# PwrSel.net
KiCad netlist of a schematic drawn in Altium Designer
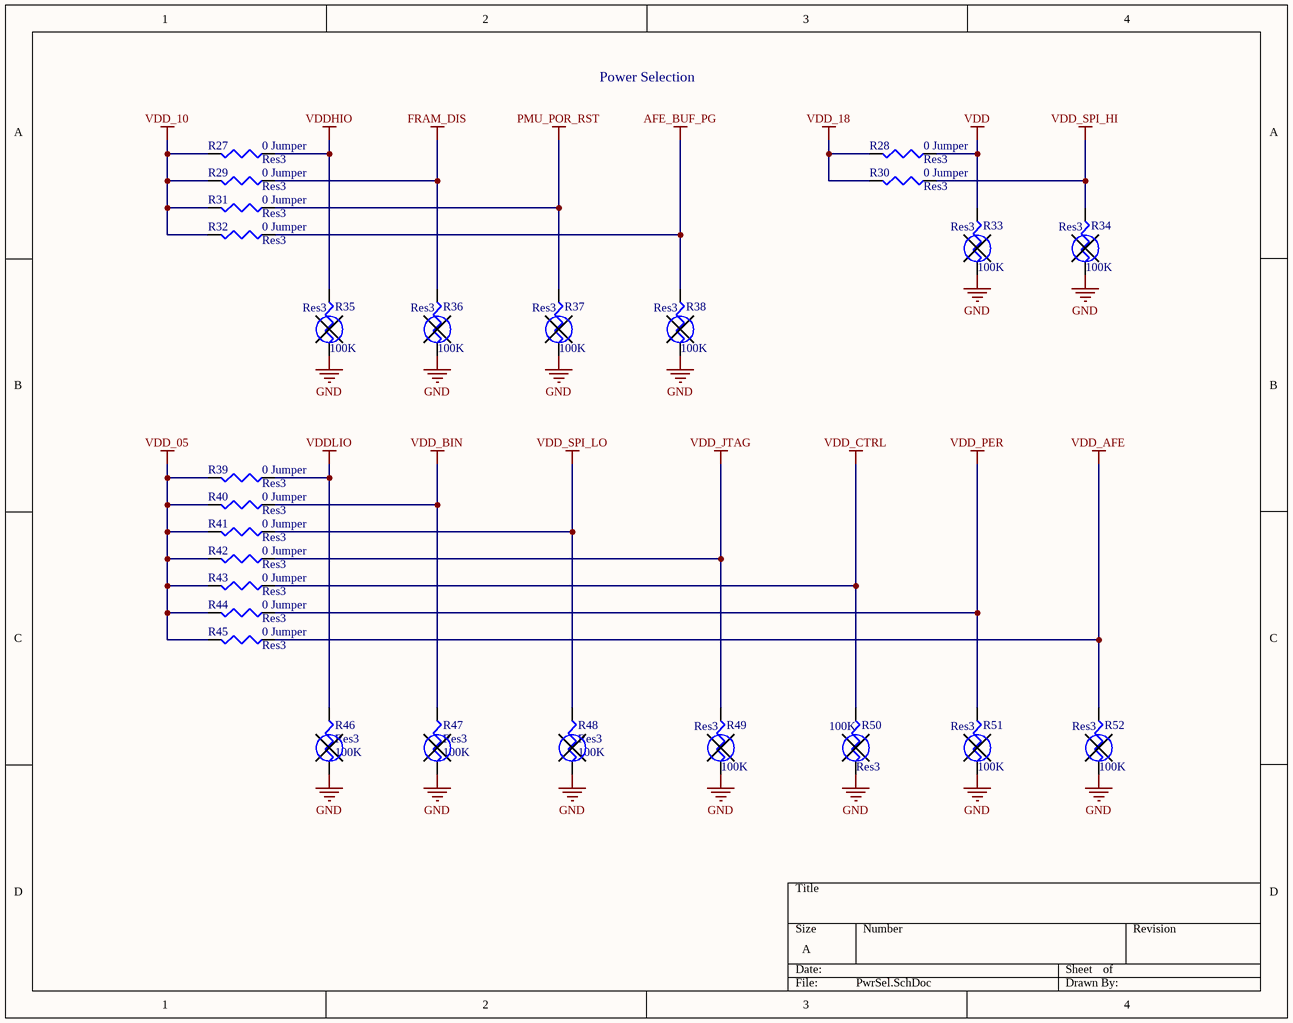
[diagram p0: PwrSel.SchDoc]

(export (version "E")
  (design (tool "Eeschema 10.0.6"))
  (components
    (comp (ref "R27")
      (value "Res3")
      (footprint "0402")
      (description "Resistor")
      (fields (field (name "ALTIUM_VALUE") "0 Jumper") (field (name "PUBLISHER") "Altium Limited"))
      (libsource (lib "Miscellaneous Devices") (part "Res3"))
    )
    (comp (ref "R28")
      (value "Res3")
      (footprint "0402")
      (description "Resistor")
      (fields (field (name "ALTIUM_VALUE") "0 Jumper") (field (name "PUBLISHER") "Altium Limited"))
      (libsource (lib "Miscellaneous Devices") (part "Res3"))
    )
    (comp (ref "R29")
      (value "Res3")
      (footprint "0402")
      (description "Resistor")
      (fields (field (name "ALTIUM_VALUE") "0 Jumper") (field (name "PUBLISHER") "Altium Limited"))
      (libsource (lib "Miscellaneous Devices") (part "Res3"))
    )
    (comp (ref "R30")
      (value "Res3")
      (footprint "0402")
      (description "Resistor")
      (fields (field (name "ALTIUM_VALUE") "0 Jumper") (field (name "PUBLISHER") "Altium Limited"))
      (libsource (lib "Miscellaneous Devices") (part "Res3"))
    )
    (comp (ref "R31")
      (value "Res3")
      (footprint "0402")
      (description "Resistor")
      (fields (field (name "ALTIUM_VALUE") "0 Jumper") (field (name "PUBLISHER") "Altium Limited"))
      (libsource (lib "Miscellaneous Devices") (part "Res3"))
    )
    (comp (ref "R32")
      (value "Res3")
      (footprint "0402")
      (description "Resistor")
      (fields (field (name "ALTIUM_VALUE") "0 Jumper") (field (name "PUBLISHER") "Altium Limited"))
      (libsource (lib "Miscellaneous Devices") (part "Res3"))
    )
    (comp (ref "R33")
      (value "Res3")
      (footprint "0402")
      (description "Resistor")
      (fields (field (name "ALTIUM_VALUE") "100K") (field (name "PUBLISHER") "Altium Limited"))
      (libsource (lib "Miscellaneous Devices") (part "Res3"))
    )
    (comp (ref "R34")
      (value "Res3")
      (footprint "0402")
      (description "Resistor")
      (fields (field (name "ALTIUM_VALUE") "100K") (field (name "PUBLISHER") "Altium Limited"))
      (libsource (lib "Miscellaneous Devices") (part "Res3"))
    )
    (comp (ref "R35")
      (value "Res3")
      (footprint "0402")
      (description "Resistor")
      (fields (field (name "ALTIUM_VALUE") "100K") (field (name "PUBLISHER") "Altium Limited"))
      (libsource (lib "Miscellaneous Devices") (part "Res3"))
    )
    (comp (ref "R36")
      (value "Res3")
      (footprint "0402")
      (description "Resistor")
      (fields (field (name "ALTIUM_VALUE") "100K") (field (name "PUBLISHER") "Altium Limited"))
      (libsource (lib "Miscellaneous Devices") (part "Res3"))
    )
    (comp (ref "R37")
      (value "Res3")
      (footprint "0402")
      (description "Resistor")
      (fields (field (name "ALTIUM_VALUE") "100K") (field (name "PUBLISHER") "Altium Limited"))
      (libsource (lib "Miscellaneous Devices") (part "Res3"))
    )
    (comp (ref "R38")
      (value "Res3")
      (footprint "0402")
      (description "Resistor")
      (fields (field (name "ALTIUM_VALUE") "100K") (field (name "PUBLISHER") "Altium Limited"))
      (libsource (lib "Miscellaneous Devices") (part "Res3"))
    )
    (comp (ref "R39")
      (value "Res3")
      (footprint "0402")
      (description "Resistor")
      (fields (field (name "ALTIUM_VALUE") "0 Jumper") (field (name "PUBLISHER") "Altium Limited"))
      (libsource (lib "Miscellaneous Devices") (part "Res3"))
    )
    (comp (ref "R40")
      (value "Res3")
      (footprint "0402")
      (description "Resistor")
      (fields (field (name "ALTIUM_VALUE") "0 Jumper") (field (name "PUBLISHER") "Altium Limited"))
      (libsource (lib "Miscellaneous Devices") (part "Res3"))
    )
    (comp (ref "R41")
      (value "Res3")
      (footprint "0402")
      (description "Resistor")
      (fields (field (name "ALTIUM_VALUE") "0 Jumper") (field (name "PUBLISHER") "Altium Limited"))
      (libsource (lib "Miscellaneous Devices") (part "Res3"))
    )
    (comp (ref "R42")
      (value "Res3")
      (footprint "0402")
      (description "Resistor")
      (fields (field (name "ALTIUM_VALUE") "0 Jumper") (field (name "PUBLISHER") "Altium Limited"))
      (libsource (lib "Miscellaneous Devices") (part "Res3"))
    )
    (comp (ref "R43")
      (value "Res3")
      (footprint "0402")
      (description "Resistor")
      (fields (field (name "ALTIUM_VALUE") "0 Jumper") (field (name "PUBLISHER") "Altium Limited"))
      (libsource (lib "Miscellaneous Devices") (part "Res3"))
    )
    (comp (ref "R44")
      (value "Res3")
      (footprint "0402")
      (description "Resistor")
      (fields (field (name "ALTIUM_VALUE") "0 Jumper") (field (name "PUBLISHER") "Altium Limited"))
      (libsource (lib "Miscellaneous Devices") (part "Res3"))
    )
    (comp (ref "R45")
      (value "Res3")
      (footprint "0402")
      (description "Resistor")
      (fields (field (name "ALTIUM_VALUE") "0 Jumper") (field (name "PUBLISHER") "Altium Limited"))
      (libsource (lib "Miscellaneous Devices") (part "Res3"))
    )
    (comp (ref "R46")
      (value "Res3")
      (footprint "0402")
      (description "Resistor")
      (fields (field (name "ALTIUM_VALUE") "100K") (field (name "PUBLISHER") "Altium Limited"))
      (libsource (lib "Miscellaneous Devices") (part "Res3"))
    )
    (comp (ref "R47")
      (value "Res3")
      (footprint "0402")
      (description "Resistor")
      (fields (field (name "ALTIUM_VALUE") "100K") (field (name "PUBLISHER") "Altium Limited"))
      (libsource (lib "Miscellaneous Devices") (part "Res3"))
    )
    (comp (ref "R48")
      (value "Res3")
      (footprint "0402")
      (description "Resistor")
      (fields (field (name "ALTIUM_VALUE") "100K") (field (name "PUBLISHER") "Altium Limited"))
      (libsource (lib "Miscellaneous Devices") (part "Res3"))
    )
    (comp (ref "R49")
      (value "Res3")
      (footprint "0402")
      (description "Resistor")
      (fields (field (name "ALTIUM_VALUE") "100K") (field (name "PUBLISHER") "Altium Limited"))
      (libsource (lib "Miscellaneous Devices") (part "Res3"))
    )
    (comp (ref "R50")
      (value "Res3")
      (footprint "0402")
      (description "Resistor")
      (fields (field (name "ALTIUM_VALUE") "100K") (field (name "PUBLISHER") "Altium Limited"))
      (libsource (lib "Miscellaneous Devices") (part "Res3"))
    )
    (comp (ref "R51")
      (value "Res3")
      (footprint "0402")
      (description "Resistor")
      (fields (field (name "ALTIUM_VALUE") "100K") (field (name "PUBLISHER") "Altium Limited"))
      (libsource (lib "Miscellaneous Devices") (part "Res3"))
    )
    (comp (ref "R52")
      (value "Res3")
      (footprint "0402")
      (description "Resistor")
      (fields (field (name "ALTIUM_VALUE") "100K") (field (name "PUBLISHER") "Altium Limited"))
      (libsource (lib "Miscellaneous Devices") (part "Res3"))
    )
  )
  (nets
    (net (code "1") (name "AFE_BUF_PG") (class "Default")
      (node (ref "R32") (pin "1") (pinfunction "1_1") (pintype "passive"))
      (node (ref "R38") (pin "1") (pinfunction "1_1") (pintype "passive"))
    )
    (net (code "2") (name "FRAM_DIS") (class "Default")
      (node (ref "R29") (pin "1") (pinfunction "1_1") (pintype "passive"))
      (node (ref "R36") (pin "1") (pinfunction "1_1") (pintype "passive"))
    )
    (net (code "3") (name "GND") (class "Default")
      (node (ref "R33") (pin "2") (pinfunction "2_2") (pintype "passive"))
      (node (ref "R34") (pin "2") (pinfunction "2_2") (pintype "passive"))
      (node (ref "R35") (pin "2") (pinfunction "2_2") (pintype "passive"))
      (node (ref "R36") (pin "2") (pinfunction "2_2") (pintype "passive"))
      (node (ref "R37") (pin "2") (pinfunction "2_2") (pintype "passive"))
      (node (ref "R38") (pin "2") (pinfunction "2_2") (pintype "passive"))
      (node (ref "R46") (pin "2") (pinfunction "2_2") (pintype "passive"))
      (node (ref "R47") (pin "2") (pinfunction "2_2") (pintype "passive"))
      (node (ref "R48") (pin "2") (pinfunction "2_2") (pintype "passive"))
      (node (ref "R49") (pin "2") (pinfunction "2_2") (pintype "passive"))
      (node (ref "R50") (pin "2") (pinfunction "2_2") (pintype "passive"))
      (node (ref "R51") (pin "2") (pinfunction "2_2") (pintype "passive"))
      (node (ref "R52") (pin "2") (pinfunction "2_2") (pintype "passive"))
    )
    (net (code "4") (name "PMU_POR_RST") (class "Default")
      (node (ref "R31") (pin "1") (pinfunction "1_1") (pintype "passive"))
      (node (ref "R37") (pin "1") (pinfunction "1_1") (pintype "passive"))
    )
    (net (code "5") (name "VDD") (class "Default")
      (node (ref "R28") (pin "1") (pinfunction "1_1") (pintype "passive"))
      (node (ref "R33") (pin "1") (pinfunction "1_1") (pintype "passive"))
    )
    (net (code "6") (name "VDDHIO") (class "Default")
      (node (ref "R27") (pin "1") (pinfunction "1_1") (pintype "passive"))
      (node (ref "R35") (pin "1") (pinfunction "1_1") (pintype "passive"))
    )
    (net (code "7") (name "VDDLIO") (class "Default")
      (node (ref "R39") (pin "1") (pinfunction "1_1") (pintype "passive"))
      (node (ref "R46") (pin "1") (pinfunction "1_1") (pintype "passive"))
    )
    (net (code "8") (name "VDD_05") (class "Default")
      (node (ref "R39") (pin "2") (pinfunction "2_2") (pintype "passive"))
      (node (ref "R40") (pin "2") (pinfunction "2_2") (pintype "passive"))
      (node (ref "R41") (pin "2") (pinfunction "2_2") (pintype "passive"))
      (node (ref "R42") (pin "2") (pinfunction "2_2") (pintype "passive"))
      (node (ref "R43") (pin "2") (pinfunction "2_2") (pintype "passive"))
      (node (ref "R44") (pin "2") (pinfunction "2_2") (pintype "passive"))
      (node (ref "R45") (pin "2") (pinfunction "2_2") (pintype "passive"))
    )
    (net (code "9") (name "VDD_10") (class "Default")
      (node (ref "R27") (pin "2") (pinfunction "2_2") (pintype "passive"))
      (node (ref "R29") (pin "2") (pinfunction "2_2") (pintype "passive"))
      (node (ref "R31") (pin "2") (pinfunction "2_2") (pintype "passive"))
      (node (ref "R32") (pin "2") (pinfunction "2_2") (pintype "passive"))
    )
    (net (code "10") (name "VDD_18") (class "Default")
      (node (ref "R28") (pin "2") (pinfunction "2_2") (pintype "passive"))
      (node (ref "R30") (pin "2") (pinfunction "2_2") (pintype "passive"))
    )
    (net (code "11") (name "VDD_AFE") (class "Default")
      (node (ref "R45") (pin "1") (pinfunction "1_1") (pintype "passive"))
      (node (ref "R52") (pin "1") (pinfunction "1_1") (pintype "passive"))
    )
    (net (code "12") (name "VDD_BIN") (class "Default")
      (node (ref "R40") (pin "1") (pinfunction "1_1") (pintype "passive"))
      (node (ref "R47") (pin "1") (pinfunction "1_1") (pintype "passive"))
    )
    (net (code "13") (name "VDD_CTRL") (class "Default")
      (node (ref "R43") (pin "1") (pinfunction "1_1") (pintype "passive"))
      (node (ref "R50") (pin "1") (pinfunction "1_1") (pintype "passive"))
    )
    (net (code "14") (name "VDD_JTAG") (class "Default")
      (node (ref "R42") (pin "1") (pinfunction "1_1") (pintype "passive"))
      (node (ref "R49") (pin "1") (pinfunction "1_1") (pintype "passive"))
    )
    (net (code "15") (name "VDD_PER") (class "Default")
      (node (ref "R44") (pin "1") (pinfunction "1_1") (pintype "passive"))
      (node (ref "R51") (pin "1") (pinfunction "1_1") (pintype "passive"))
    )
    (net (code "16") (name "VDD_SPI_HI") (class "Default")
      (node (ref "R30") (pin "1") (pinfunction "1_1") (pintype "passive"))
      (node (ref "R34") (pin "1") (pinfunction "1_1") (pintype "passive"))
    )
    (net (code "17") (name "VDD_SPI_LO") (class "Default")
      (node (ref "R41") (pin "1") (pinfunction "1_1") (pintype "passive"))
      (node (ref "R48") (pin "1") (pinfunction "1_1") (pintype "passive"))
    )
  )
)
